# arduino_mega_giga_shield_template.net
KiCad netlist of a schematic drawn in Altium Designer
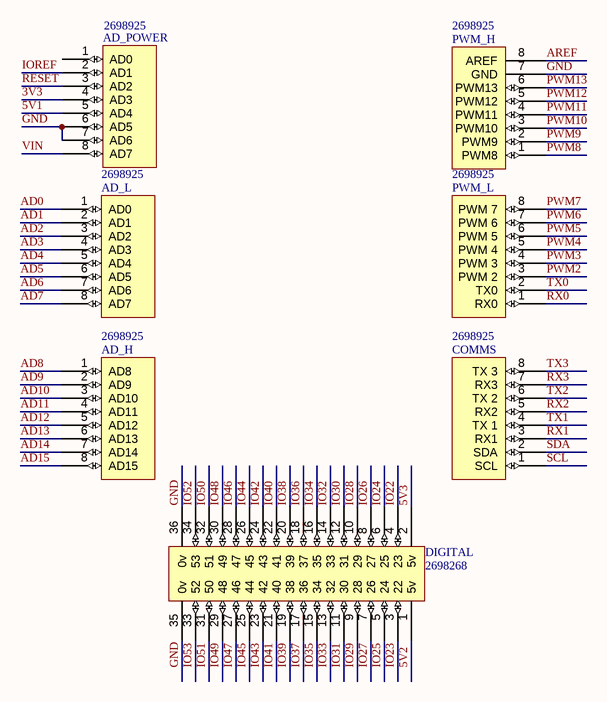
[diagram p0: arduino_mega_giga_shield_template.SchDoc]

(export (version "E")
  (design (tool "Eeschema 10.0.6"))
  (components
    (comp (ref "AD_H")
      (value "AD_H")
      (footprint "Header 8x1 8.5mm")
      (fields (field (name "SUPPLIER PART NUMBER 4") "2698925"))
      (libsource (lib "Header") (part "AD_H"))
    )
    (comp (ref "AD_L")
      (value "AD_L")
      (footprint "Header 8x1 8.5mm")
      (fields (field (name "SUPPLIER PART NUMBER 5") "2698925"))
      (libsource (lib "Header") (part "AD_L"))
    )
    (comp (ref "AD_POWER")
      (value "AD_POWER")
      (footprint "Header 8x1 8.5mm")
      (fields (field (name "SUPPLIER PART NUMBER 5") "2698925"))
      (libsource (lib "Header") (part "AD_L"))
    )
    (comp (ref "COMMS")
      (value "Communication")
      (footprint "Header 8x1 8.5mm")
      (fields (field (name "SUPPLIER PART NUMBER 4") "2698925"))
      (libsource (lib "Header") (part "Communication"))
    )
    (comp (ref "DIGITAL")
      (value "IO_36")
      (footprint "HEADER 36X 8MM")
      (fields (field (name "SUPPLIER PART NUMBER 5") "2698268"))
      (libsource (lib "Header") (part "IO_36"))
    )
    (comp (ref "PWM_H")
      (value "PWM_H")
      (footprint "Header 8x1 8.5mm")
      (fields (field (name "SUPPLIER PART NUMBER 4") "2698925"))
      (libsource (lib "Header") (part "PWM_H"))
    )
    (comp (ref "PWM_L")
      (value "PWM_L")
      (footprint "Header 8x1 8.5mm")
      (fields (field (name "SUPPLIER PART NUMBER 4") "2698925"))
      (libsource (lib "Header") (part "PWM_L"))
    )
  )
  (nets
    (net (code "1") (name "/3V3") (class "Default")
      (node (ref "AD_POWER") (pin "4") (pinfunction "AD3_4") (pintype "bidirectional"))
    )
    (net (code "2") (name "/5V1") (class "Default")
      (node (ref "AD_POWER") (pin "5") (pinfunction "AD4_5") (pintype "bidirectional"))
    )
    (net (code "3") (name "/5V2") (class "Default")
      (node (ref "DIGITAL") (pin "1") (pinfunction "5v_1") (pintype "power_in"))
    )
    (net (code "4") (name "/5V3") (class "Default")
      (node (ref "DIGITAL") (pin "2") (pinfunction "5v_2") (pintype "power_in"))
    )
    (net (code "5") (name "/AD0") (class "Default")
      (node (ref "AD_L") (pin "1") (pinfunction "AD0_1") (pintype "bidirectional"))
    )
    (net (code "6") (name "/AD1") (class "Default")
      (node (ref "AD_L") (pin "2") (pinfunction "AD1_2") (pintype "bidirectional"))
    )
    (net (code "7") (name "/AD2") (class "Default")
      (node (ref "AD_L") (pin "3") (pinfunction "AD2_3") (pintype "bidirectional"))
    )
    (net (code "8") (name "/AD3") (class "Default")
      (node (ref "AD_L") (pin "4") (pinfunction "AD3_4") (pintype "bidirectional"))
    )
    (net (code "9") (name "/AD4") (class "Default")
      (node (ref "AD_L") (pin "5") (pinfunction "AD4_5") (pintype "bidirectional"))
    )
    (net (code "10") (name "/AD5") (class "Default")
      (node (ref "AD_L") (pin "6") (pinfunction "AD5_6") (pintype "bidirectional"))
    )
    (net (code "11") (name "/AD6") (class "Default")
      (node (ref "AD_L") (pin "7") (pinfunction "AD6_7") (pintype "bidirectional"))
    )
    (net (code "12") (name "/AD7") (class "Default")
      (node (ref "AD_L") (pin "8") (pinfunction "AD7_8") (pintype "bidirectional"))
    )
    (net (code "13") (name "/AD8") (class "Default")
      (node (ref "AD_H") (pin "1") (pinfunction "AD8_1") (pintype "bidirectional"))
    )
    (net (code "14") (name "/AD9") (class "Default")
      (node (ref "AD_H") (pin "2") (pinfunction "AD9_2") (pintype "bidirectional"))
    )
    (net (code "15") (name "/AD10") (class "Default")
      (node (ref "AD_H") (pin "3") (pinfunction "AD10_3") (pintype "bidirectional"))
    )
    (net (code "16") (name "/AD11") (class "Default")
      (node (ref "AD_H") (pin "4") (pinfunction "AD11_4") (pintype "bidirectional"))
    )
    (net (code "17") (name "/AD12") (class "Default")
      (node (ref "AD_H") (pin "5") (pinfunction "AD12_5") (pintype "bidirectional"))
    )
    (net (code "18") (name "/AD13") (class "Default")
      (node (ref "AD_H") (pin "6") (pinfunction "AD13_6") (pintype "bidirectional"))
    )
    (net (code "19") (name "/AD14") (class "Default")
      (node (ref "AD_H") (pin "7") (pinfunction "AD14_7") (pintype "bidirectional"))
    )
    (net (code "20") (name "/AD15") (class "Default")
      (node (ref "AD_H") (pin "8") (pinfunction "AD15_8") (pintype "bidirectional"))
    )
    (net (code "21") (name "/AREF") (class "Default")
      (node (ref "PWM_H") (pin "8") (pinfunction "AREF_8") (pintype "passive"))
    )
    (net (code "22") (name "/GND") (class "Default")
      (node (ref "AD_POWER") (pin "6") (pinfunction "AD5_6") (pintype "bidirectional"))
      (node (ref "AD_POWER") (pin "7") (pinfunction "AD6_7") (pintype "bidirectional"))
      (node (ref "DIGITAL") (pin "35") (pinfunction "0v_35") (pintype "power_in"))
      (node (ref "DIGITAL") (pin "36") (pinfunction "0v_36") (pintype "power_in"))
      (node (ref "PWM_H") (pin "7") (pinfunction "GND_7") (pintype "power_in"))
    )
    (net (code "23") (name "/IO22") (class "Default")
      (node (ref "DIGITAL") (pin "4") (pinfunction "23_4") (pintype "bidirectional"))
    )
    (net (code "24") (name "/IO23") (class "Default")
      (node (ref "DIGITAL") (pin "3") (pinfunction "22_3") (pintype "bidirectional"))
    )
    (net (code "25") (name "/IO24") (class "Default")
      (node (ref "DIGITAL") (pin "6") (pinfunction "25_6") (pintype "bidirectional"))
    )
    (net (code "26") (name "/IO25") (class "Default")
      (node (ref "DIGITAL") (pin "5") (pinfunction "24_5") (pintype "bidirectional"))
    )
    (net (code "27") (name "/IO26") (class "Default")
      (node (ref "DIGITAL") (pin "8") (pinfunction "27_8") (pintype "bidirectional"))
    )
    (net (code "28") (name "/IO27") (class "Default")
      (node (ref "DIGITAL") (pin "7") (pinfunction "26_7") (pintype "bidirectional"))
    )
    (net (code "29") (name "/IO28") (class "Default")
      (node (ref "DIGITAL") (pin "10") (pinfunction "29_10") (pintype "bidirectional"))
    )
    (net (code "30") (name "/IO29") (class "Default")
      (node (ref "DIGITAL") (pin "9") (pinfunction "28_9") (pintype "bidirectional"))
    )
    (net (code "31") (name "/IO30") (class "Default")
      (node (ref "DIGITAL") (pin "12") (pinfunction "31_12") (pintype "bidirectional"))
    )
    (net (code "32") (name "/IO31") (class "Default")
      (node (ref "DIGITAL") (pin "11") (pinfunction "30_11") (pintype "bidirectional"))
    )
    (net (code "33") (name "/IO32") (class "Default")
      (node (ref "DIGITAL") (pin "14") (pinfunction "33_14") (pintype "bidirectional"))
    )
    (net (code "34") (name "/IO33") (class "Default")
      (node (ref "DIGITAL") (pin "13") (pinfunction "32_13") (pintype "bidirectional"))
    )
    (net (code "35") (name "/IO34") (class "Default")
      (node (ref "DIGITAL") (pin "16") (pinfunction "35_16") (pintype "bidirectional"))
    )
    (net (code "36") (name "/IO35") (class "Default")
      (node (ref "DIGITAL") (pin "15") (pinfunction "34_15") (pintype "bidirectional"))
    )
    (net (code "37") (name "/IO36") (class "Default")
      (node (ref "DIGITAL") (pin "18") (pinfunction "37_18") (pintype "bidirectional"))
    )
    (net (code "38") (name "/IO37") (class "Default")
      (node (ref "DIGITAL") (pin "17") (pinfunction "36_17") (pintype "bidirectional"))
    )
    (net (code "39") (name "/IO38") (class "Default")
      (node (ref "DIGITAL") (pin "20") (pinfunction "39_20") (pintype "bidirectional"))
    )
    (net (code "40") (name "/IO39") (class "Default")
      (node (ref "DIGITAL") (pin "19") (pinfunction "38_19") (pintype "bidirectional"))
    )
    (net (code "41") (name "/IO40") (class "Default")
      (node (ref "DIGITAL") (pin "22") (pinfunction "41_22") (pintype "bidirectional"))
    )
    (net (code "42") (name "/IO41") (class "Default")
      (node (ref "DIGITAL") (pin "21") (pinfunction "40_21") (pintype "bidirectional"))
    )
    (net (code "43") (name "/IO42") (class "Default")
      (node (ref "DIGITAL") (pin "24") (pinfunction "43_24") (pintype "bidirectional"))
    )
    (net (code "44") (name "/IO43") (class "Default")
      (node (ref "DIGITAL") (pin "23") (pinfunction "42_23") (pintype "bidirectional"))
    )
    (net (code "45") (name "/IO44") (class "Default")
      (node (ref "DIGITAL") (pin "26") (pinfunction "45_26") (pintype "bidirectional"))
    )
    (net (code "46") (name "/IO45") (class "Default")
      (node (ref "DIGITAL") (pin "25") (pinfunction "44_25") (pintype "bidirectional"))
    )
    (net (code "47") (name "/IO46") (class "Default")
      (node (ref "DIGITAL") (pin "28") (pinfunction "47_28") (pintype "bidirectional"))
    )
    (net (code "48") (name "/IO47") (class "Default")
      (node (ref "DIGITAL") (pin "27") (pinfunction "46_27") (pintype "bidirectional"))
    )
    (net (code "49") (name "/IO48") (class "Default")
      (node (ref "DIGITAL") (pin "30") (pinfunction "49_30") (pintype "bidirectional"))
    )
    (net (code "50") (name "/IO49") (class "Default")
      (node (ref "DIGITAL") (pin "29") (pinfunction "48_29") (pintype "bidirectional"))
    )
    (net (code "51") (name "/IO50") (class "Default")
      (node (ref "DIGITAL") (pin "32") (pinfunction "51_32") (pintype "bidirectional"))
    )
    (net (code "52") (name "/IO51") (class "Default")
      (node (ref "DIGITAL") (pin "31") (pinfunction "50_31") (pintype "bidirectional"))
    )
    (net (code "53") (name "/IO52") (class "Default")
      (node (ref "DIGITAL") (pin "34") (pinfunction "53_34") (pintype "bidirectional"))
    )
    (net (code "54") (name "/IO53") (class "Default")
      (node (ref "DIGITAL") (pin "33") (pinfunction "52_33") (pintype "bidirectional"))
    )
    (net (code "55") (name "/IOREF") (class "Default")
      (node (ref "AD_POWER") (pin "2") (pinfunction "AD1_2") (pintype "bidirectional"))
    )
    (net (code "56") (name "/PWM2") (class "Default")
      (node (ref "PWM_L") (pin "3") (pinfunction "PWM_2_3") (pintype "bidirectional"))
    )
    (net (code "57") (name "/PWM3") (class "Default")
      (node (ref "PWM_L") (pin "4") (pinfunction "PWM_3_4") (pintype "bidirectional"))
    )
    (net (code "58") (name "/PWM4") (class "Default")
      (node (ref "PWM_L") (pin "5") (pinfunction "PWM_4_5") (pintype "bidirectional"))
    )
    (net (code "59") (name "/PWM5") (class "Default")
      (node (ref "PWM_L") (pin "6") (pinfunction "PWM_5_6") (pintype "bidirectional"))
    )
    (net (code "60") (name "/PWM6") (class "Default")
      (node (ref "PWM_L") (pin "7") (pinfunction "PWM_6_7") (pintype "bidirectional"))
    )
    (net (code "61") (name "/PWM7") (class "Default")
      (node (ref "PWM_L") (pin "8") (pinfunction "PWM_7_8") (pintype "bidirectional"))
    )
    (net (code "62") (name "/PWM8") (class "Default")
      (node (ref "PWM_H") (pin "1") (pinfunction "PWM8_1") (pintype "bidirectional"))
    )
    (net (code "63") (name "/PWM9") (class "Default")
      (node (ref "PWM_H") (pin "2") (pinfunction "PWM9_2") (pintype "bidirectional"))
    )
    (net (code "64") (name "/PWM10") (class "Default")
      (node (ref "PWM_H") (pin "3") (pinfunction "PWM10_3") (pintype "bidirectional"))
    )
    (net (code "65") (name "/PWM11") (class "Default")
      (node (ref "PWM_H") (pin "4") (pinfunction "PWM11_4") (pintype "bidirectional"))
    )
    (net (code "66") (name "/PWM12") (class "Default")
      (node (ref "PWM_H") (pin "5") (pinfunction "PWM12_5") (pintype "bidirectional"))
    )
    (net (code "67") (name "/PWM13") (class "Default")
      (node (ref "PWM_H") (pin "6") (pinfunction "PWM13_6") (pintype "bidirectional"))
    )
    (net (code "68") (name "/RESET") (class "Default")
      (node (ref "AD_POWER") (pin "3") (pinfunction "AD2_3") (pintype "bidirectional"))
    )
    (net (code "69") (name "/RX0") (class "Default")
      (node (ref "PWM_L") (pin "1") (pinfunction "RX0_1") (pintype "bidirectional"))
    )
    (net (code "70") (name "/RX1") (class "Default")
      (node (ref "COMMS") (pin "3") (pinfunction "RX1_3") (pintype "bidirectional"))
    )
    (net (code "71") (name "/RX2") (class "Default")
      (node (ref "COMMS") (pin "5") (pinfunction "RX2_5") (pintype "bidirectional"))
    )
    (net (code "72") (name "/RX3") (class "Default")
      (node (ref "COMMS") (pin "7") (pinfunction "RX3_7") (pintype "bidirectional"))
    )
    (net (code "73") (name "/SCL") (class "Default")
      (node (ref "COMMS") (pin "1") (pinfunction "SCL_1") (pintype "bidirectional"))
    )
    (net (code "74") (name "/SDA") (class "Default")
      (node (ref "COMMS") (pin "2") (pinfunction "SDA_2") (pintype "bidirectional"))
    )
    (net (code "75") (name "/TX0") (class "Default")
      (node (ref "PWM_L") (pin "2") (pinfunction "TX0_2") (pintype "bidirectional"))
    )
    (net (code "76") (name "/TX1") (class "Default")
      (node (ref "COMMS") (pin "4") (pinfunction "TX_1_4") (pintype "bidirectional"))
    )
    (net (code "77") (name "/TX2") (class "Default")
      (node (ref "COMMS") (pin "6") (pinfunction "TX_2_6") (pintype "bidirectional"))
    )
    (net (code "78") (name "/TX3") (class "Default")
      (node (ref "COMMS") (pin "8") (pinfunction "TX_3_8") (pintype "bidirectional"))
    )
    (net (code "79") (name "/VIN") (class "Default")
      (node (ref "AD_POWER") (pin "8") (pinfunction "AD7_8") (pintype "bidirectional"))
    )
    (net (code "80") (name "unconnected-(AD_POWER-AD0-Pad1)") (class "Default")
      (node (ref "AD_POWER") (pin "1") (pinfunction "AD0_1") (pintype "bidirectional"))
    )
  )
)
